# 2_4G.net
KiCad netlist of a schematic drawn in Altium Designer
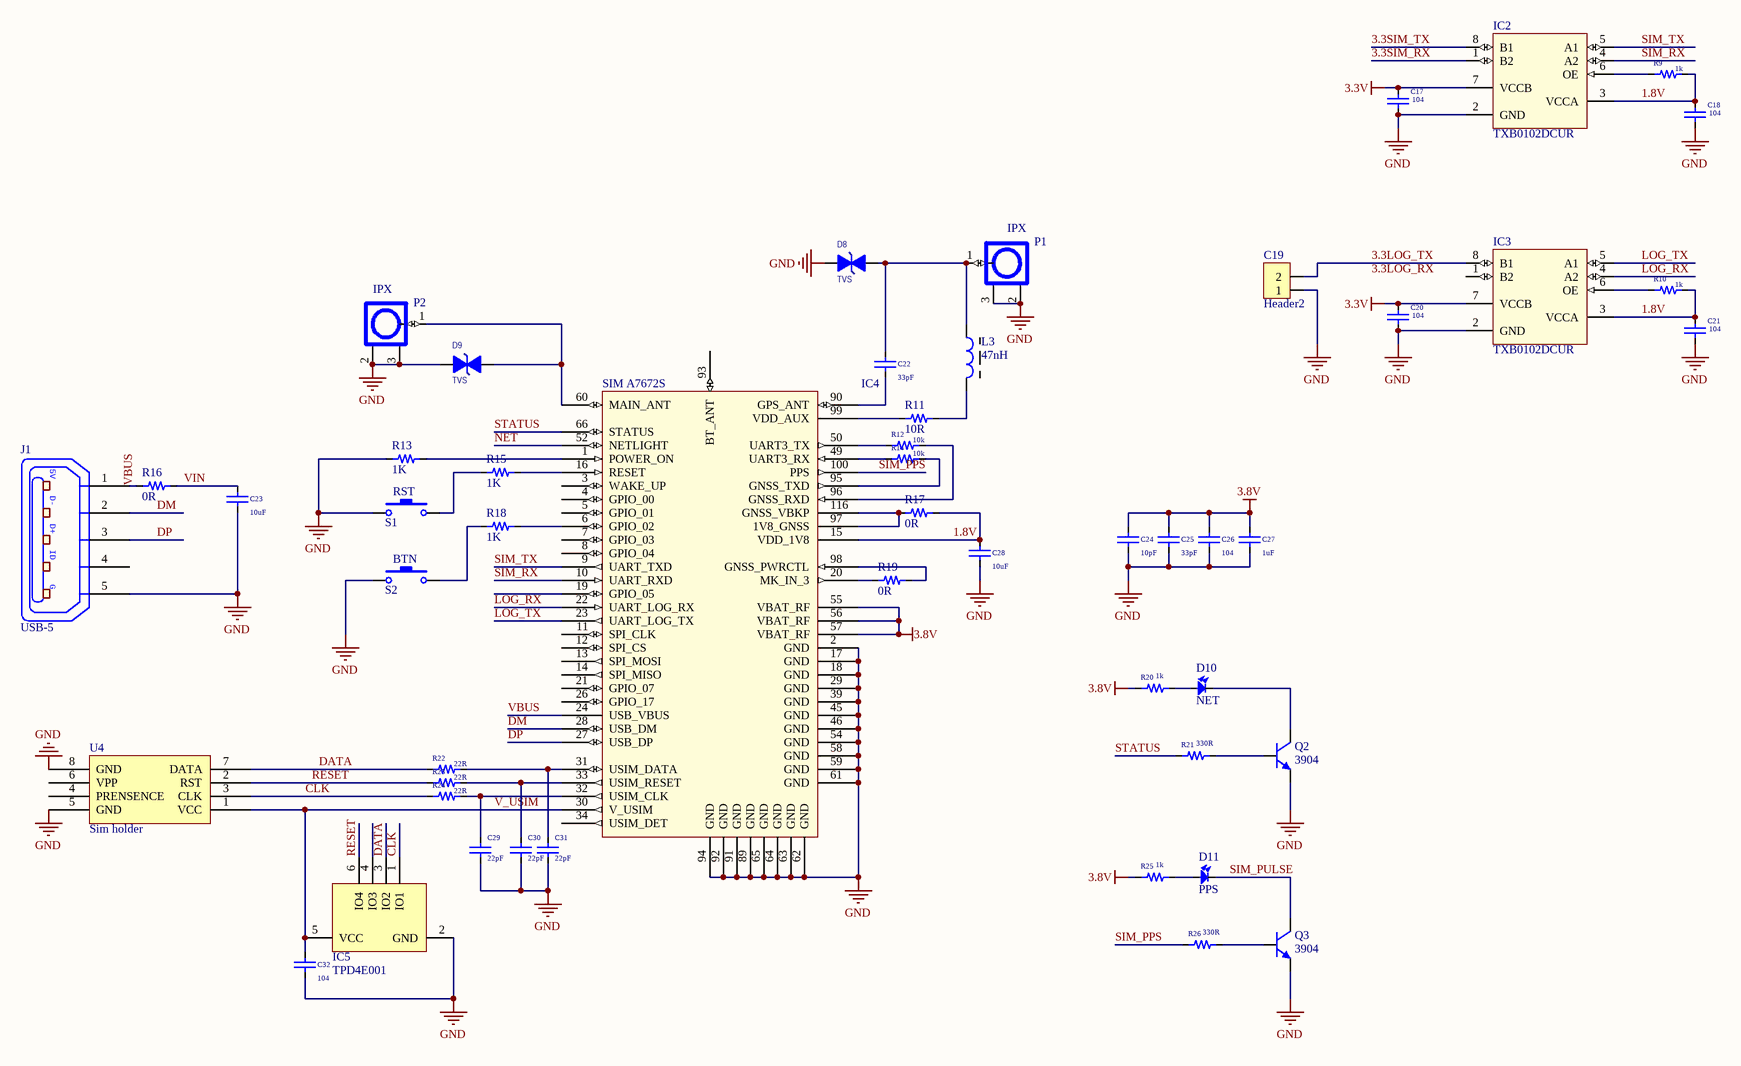
[diagram p0: 2. 4G.SchDoc]

(export (version "E")
  (design (tool "Eeschema 10.0.6"))
  (components
    (comp (ref "C17")
      (value "104")
      (footprint "CAP_0603")
      (description "Capacitor")
      (fields (field (name "PUBLISHER") "Altium Limited"))
      (libsource (lib "My Library") (part "CapSMD"))
    )
    (comp (ref "C18")
      (value "104")
      (footprint "CAP_0603")
      (description "Capacitor")
      (fields (field (name "PUBLISHER") "Altium Limited"))
      (libsource (lib "My Library") (part "CapSMD"))
    )
    (comp (ref "C19")
      (value "Header2")
      (footprint "JP2")
      (description "Header IDC, 2 x 1 Pin Vertical 2.54mm Pitch (Non-Boxed, Male)")
      (fields
        (field (name "MANUFACTURER") "Würth Elektronik eiSos GmbH")
        (field (name "PARTNO") "613002143121")
        (field (name "CREATED BY") "Karrer Zheng")
      )
      (libsource (lib "My Library") (part "Header2"))
    )
    (comp (ref "C20")
      (value "104")
      (footprint "CAP_0603")
      (description "Capacitor")
      (fields (field (name "PUBLISHER") "Altium Limited"))
      (libsource (lib "My Library") (part "CapSMD"))
    )
    (comp (ref "C21")
      (value "104")
      (footprint "CAP_0603")
      (description "Capacitor")
      (fields (field (name "PUBLISHER") "Altium Limited"))
      (libsource (lib "My Library") (part "CapSMD"))
    )
    (comp (ref "C22")
      (value "33pF")
      (footprint "CAP_0603")
      (description "Capacitor")
      (fields (field (name "PUBLISHER") "Altium Limited"))
      (libsource (lib "My Library") (part "CapSMD"))
    )
    (comp (ref "C23")
      (value "10uF")
      (footprint "CAP_0603")
      (description "Capacitor")
      (fields (field (name "PUBLISHER") "Altium Limited"))
      (libsource (lib "My Library") (part "CapSMD"))
    )
    (comp (ref "C24")
      (value "10pF")
      (footprint "CAP_0603")
      (description "Capacitor")
      (fields (field (name "PUBLISHER") "Altium Limited"))
      (libsource (lib "My Library") (part "CapSMD"))
    )
    (comp (ref "C25")
      (value "33pF")
      (footprint "CAP_0603")
      (description "Capacitor")
      (fields (field (name "PUBLISHER") "Altium Limited"))
      (libsource (lib "My Library") (part "CapSMD"))
    )
    (comp (ref "C26")
      (value "104")
      (footprint "CAP_0603")
      (description "Capacitor")
      (fields (field (name "PUBLISHER") "Altium Limited"))
      (libsource (lib "My Library") (part "CapSMD"))
    )
    (comp (ref "C27")
      (value "1uF")
      (footprint "CAP_0603")
      (description "Capacitor")
      (fields (field (name "PUBLISHER") "Altium Limited"))
      (libsource (lib "My Library") (part "CapSMD"))
    )
    (comp (ref "C28")
      (value "10uF")
      (footprint "CAP_0603")
      (description "Capacitor")
      (fields (field (name "PUBLISHER") "Altium Limited"))
      (libsource (lib "My Library") (part "CapSMD"))
    )
    (comp (ref "C29")
      (value "22pF")
      (footprint "CAP_0603")
      (description "Capacitor")
      (fields (field (name "PUBLISHER") "Altium Limited"))
      (libsource (lib "My Library") (part "CapSMD"))
    )
    (comp (ref "C30")
      (value "22pF")
      (footprint "CAP_0603")
      (description "Capacitor")
      (fields (field (name "PUBLISHER") "Altium Limited"))
      (libsource (lib "My Library") (part "CapSMD"))
    )
    (comp (ref "C31")
      (value "22pF")
      (footprint "CAP_0603")
      (description "Capacitor")
      (fields (field (name "PUBLISHER") "Altium Limited"))
      (libsource (lib "My Library") (part "CapSMD"))
    )
    (comp (ref "C32")
      (value "104")
      (footprint "CAP_0603")
      (description "Capacitor")
      (fields (field (name "PUBLISHER") "Altium Limited"))
      (libsource (lib "My Library") (part "CapSMD"))
    )
    (comp (ref "D8")
      (value "TVS")
      (footprint "RES-SMD-0402")
      (description "TVS DIODE 4VWM 1005")
      (fields
        (field (name "MANUFACTURER") "Murata Electronics")
        (field (name "PART NUMBER") "LXES15AAA1-153")
      )
      (libsource (lib "My Library") (part "TVS"))
    )
    (comp (ref "D9")
      (value "TVS")
      (footprint "RES-SMD-0402")
      (description "TVS DIODE 4VWM 1005")
      (fields
        (field (name "MANUFACTURER") "Murata Electronics")
        (field (name "PART NUMBER") "LXES15AAA1-153")
      )
      (libsource (lib "My Library") (part "TVS"))
    )
    (comp (ref "D10")
      (value "NET")
      (footprint "LED-3")
      (description "LED Single colour Green and Red")
      (libsource (lib "My Library") (part "LED"))
    )
    (comp (ref "D11")
      (value "PPS")
      (footprint "LED-0603-Red")
      (description "LED Single colour Green and Red")
      (libsource (lib "My Library") (part "LED"))
    )
    (comp (ref "IC2")
      (value "TXB0102DCUR")
      (footprint "TXB0102DCUR")
      (description "IC TRNSLTR BIDIRECTIONAL US8")
      (fields (field (name "MANUFACTURER") "Texas Instruments"))
      (libsource (lib "My Library") (part "TXB0102DCUR"))
    )
    (comp (ref "IC3")
      (value "TXB0102DCUR")
      (footprint "TXB0102DCUR")
      (description "IC TRNSLTR BIDIRECTIONAL US8")
      (fields (field (name "MANUFACTURER") "Texas Instruments"))
      (libsource (lib "My Library") (part "TXB0102DCUR"))
    )
    (comp (ref "IC4")
      (value "SIM A7672S")
      (footprint "SIM A7672S")
      (description "SIM A7672S-CAT-M1")
      (libsource (lib "My Library") (part "SIM A7672S"))
    )
    (comp (ref "IC5")
      (value "TPD4E001")
      (footprint "TPD4E001")
      (fields (field (name "MANUFACTURER") "Texas Instruments") (field (name "PART NUMBER") "TPD4E001RDBVR"))
      (libsource (lib "My Library") (part "TPD4E001_1"))
    )
    (comp (ref "J1")
      (value "USB-5")
      (footprint "MICROUSB")
      (fields (field (name "MANUFACTURER") "FCI"))
      (libsource (lib "Anh_Trung") (part "USB-5"))
    )
    (comp (ref "L3")
      (value "47nH")
      (footprint "RES-SMD-0603")
      (description "FIXED IND 47NH 300MA 700MOHM SMD")
      (fields (field (name "MANUFACTURER") "Taiyo Yuden") (field (name "PART NUMBER") "HK160847NJ-T"))
      (libsource (lib "Anh_Trung") (part "Inductor Ferit"))
    )
    (comp (ref "P1")
      (value "IPX")
      (footprint "IPXS")
      (description "Antenna GSM GPS")
      (fields
        (field (name "MANUFACTURER") "TE Connectivity AMP Connectors")
        (field (name "PART NUMBER") "2334884-1")
      )
      (libsource (lib "") (part "IPXSx66_1"))
    )
    (comp (ref "P2")
      (value "IPX")
      (footprint "IPXS")
      (description "Antenna GSM GPS")
      (fields
        (field (name "MANUFACTURER") "TE Connectivity AMP Connectors")
        (field (name "PART NUMBER") "2334884-1")
      )
      (libsource (lib "Anh_Trung") (part "IPXSx66"))
    )
    (comp (ref "Q2") (value "3904") (footprint "MMBT3904") (libsource (lib "My Library") (part "MMBT3904")))
    (comp (ref "Q3") (value "3904") (footprint "MMBT3904") (libsource (lib "My Library") (part "MMBT3904")))
    (comp (ref "R9")
      (value "1k")
      (footprint "RES-SMD-0603")
      (description "Resistor")
      (fields
        (field (name "MANUFACTURER") "Generic Components")
        (field (name "PUBLISHER") "Altium Hobart Technology Centre")
      )
      (libsource (lib "My Library") (part "Resistor - SMD"))
    )
    (comp (ref "R10")
      (value "1k")
      (footprint "RES-SMD-0603")
      (description "Resistor")
      (fields
        (field (name "MANUFACTURER") "Generic Components")
        (field (name "PUBLISHER") "Altium Hobart Technology Centre")
      )
      (libsource (lib "My Library") (part "Resistor - SMD"))
    )
    (comp (ref "R11")
      (value "10R")
      (footprint "RES-SMD-0603")
      (description "Resistor")
      (fields
        (field (name "MANUFACTURER") "Generic Components")
        (field (name "PUBLISHER") "Altium Hobart Technology Centre")
      )
      (libsource (lib "My Library") (part "Resistor - SMD"))
    )
    (comp (ref "R12")
      (value "10k")
      (footprint "RES-SMD-0603")
      (description "Resistor")
      (fields
        (field (name "MANUFACTURER") "Generic Components")
        (field (name "PUBLISHER") "Altium Hobart Technology Centre")
      )
      (libsource (lib "My Library") (part "Resistor - SMD"))
    )
    (comp (ref "R13")
      (value "1K")
      (footprint "RES-SMD-0603")
      (description "Resistor")
      (fields
        (field (name "MANUFACTURER") "Generic Components")
        (field (name "PUBLISHER") "Altium Hobart Technology Centre")
      )
      (libsource (lib "My Library") (part "Resistor - SMD"))
    )
    (comp (ref "R14")
      (value "10k")
      (footprint "RES-SMD-0603")
      (description "Resistor")
      (fields
        (field (name "MANUFACTURER") "Generic Components")
        (field (name "PUBLISHER") "Altium Hobart Technology Centre")
      )
      (libsource (lib "My Library") (part "Resistor - SMD"))
    )
    (comp (ref "R15")
      (value "1K")
      (footprint "RES-SMD-0603")
      (description "Resistor")
      (fields
        (field (name "MANUFACTURER") "Generic Components")
        (field (name "PUBLISHER") "Altium Hobart Technology Centre")
      )
      (libsource (lib "My Library") (part "Resistor - SMD"))
    )
    (comp (ref "R16")
      (value "0R")
      (footprint "RES-SMD-0603")
      (description "Resistor")
      (fields
        (field (name "MANUFACTURER") "Generic Components")
        (field (name "PUBLISHER") "Altium Hobart Technology Centre")
      )
      (libsource (lib "My Library") (part "Resistor - SMD"))
    )
    (comp (ref "R17")
      (value "0R")
      (footprint "RES-SMD-0603")
      (description "Resistor")
      (fields
        (field (name "MANUFACTURER") "Generic Components")
        (field (name "PUBLISHER") "Altium Hobart Technology Centre")
      )
      (libsource (lib "My Library") (part "Resistor - SMD"))
    )
    (comp (ref "R18")
      (value "1K")
      (footprint "RES-SMD-0603")
      (description "Resistor")
      (fields
        (field (name "MANUFACTURER") "Generic Components")
        (field (name "PUBLISHER") "Altium Hobart Technology Centre")
      )
      (libsource (lib "My Library") (part "Resistor - SMD"))
    )
    (comp (ref "R19")
      (value "0R")
      (footprint "RES-SMD-0603")
      (description "Resistor")
      (fields
        (field (name "MANUFACTURER") "Generic Components")
        (field (name "PUBLISHER") "Altium Hobart Technology Centre")
      )
      (libsource (lib "My Library") (part "Resistor - SMD"))
    )
    (comp (ref "R20")
      (value "1k")
      (footprint "RES-SMD-0603")
      (description "Resistor")
      (fields
        (field (name "MANUFACTURER") "Generic Components")
        (field (name "PUBLISHER") "Altium Hobart Technology Centre")
      )
      (libsource (lib "My Library") (part "Resistor - SMD"))
    )
    (comp (ref "R21")
      (value "330R")
      (footprint "RES-SMD-0603")
      (description "Resistor")
      (fields
        (field (name "MANUFACTURER") "Generic Components")
        (field (name "PUBLISHER") "Altium Hobart Technology Centre")
      )
      (libsource (lib "My Library") (part "Resistor - SMD"))
    )
    (comp (ref "R22")
      (value "22R")
      (footprint "RES-SMD-0603")
      (description "Resistor")
      (fields
        (field (name "MANUFACTURER") "Generic Components")
        (field (name "PUBLISHER") "Altium Hobart Technology Centre")
      )
      (libsource (lib "My Library") (part "Resistor - SMD"))
    )
    (comp (ref "R23")
      (value "22R")
      (footprint "RES-SMD-0603")
      (description "Resistor")
      (fields
        (field (name "MANUFACTURER") "Generic Components")
        (field (name "PUBLISHER") "Altium Hobart Technology Centre")
      )
      (libsource (lib "My Library") (part "Resistor - SMD"))
    )
    (comp (ref "R24")
      (value "22R")
      (footprint "RES-SMD-0603")
      (description "Resistor")
      (fields
        (field (name "MANUFACTURER") "Generic Components")
        (field (name "PUBLISHER") "Altium Hobart Technology Centre")
      )
      (libsource (lib "My Library") (part "Resistor - SMD"))
    )
    (comp (ref "R25")
      (value "1k")
      (footprint "RES-SMD-0603")
      (description "Resistor")
      (fields
        (field (name "MANUFACTURER") "Generic Components")
        (field (name "PUBLISHER") "Altium Hobart Technology Centre")
      )
      (libsource (lib "My Library") (part "Resistor - SMD"))
    )
    (comp (ref "R26")
      (value "330R")
      (footprint "RES-SMD-0603")
      (description "Resistor")
      (fields
        (field (name "MANUFACTURER") "Generic Components")
        (field (name "PUBLISHER") "Altium Hobart Technology Centre")
      )
      (libsource (lib "My Library") (part "Resistor - SMD"))
    )
    (comp (ref "S1")
      (value "RST")
      (footprint "SW-SMD")
      (description "Switch")
      (fields (field (name "PUBLISHER") "Altium Limited"))
      (libsource (lib "My Library") (part "SW-SMD"))
    )
    (comp (ref "S2")
      (value "BTN")
      (footprint "SW-SMD")
      (description "Switch")
      (fields (field (name "PUBLISHER") "Altium Limited"))
      (libsource (lib "My Library") (part "SW-SMD"))
    )
    (comp (ref "U4")
      (value "Sim holder")
      (footprint "SIM_MicroSIM 6P Flip")
      (libsource (lib "Anh_Trung") (part "Component_1"))
    )
  )
  (nets
    (net (code "1") (name "/1.8V") (class "Default")
      (node (ref "C18") (pin "2") (pinfunction "2_2") (pintype "passive"))
      (node (ref "C21") (pin "2") (pinfunction "2_2") (pintype "passive"))
      (node (ref "C28") (pin "2") (pinfunction "2_2") (pintype "passive"))
      (node (ref "IC2") (pin "3") (pinfunction "VCCA_3") (pintype "power_in"))
      (node (ref "IC3") (pin "3") (pinfunction "VCCA_3") (pintype "power_in"))
      (node (ref "IC4") (pin "15") (pinfunction "VDD_1V8_15") (pintype "passive"))
      (node (ref "R10") (pin "1") (pinfunction "1_1") (pintype "passive"))
      (node (ref "R17") (pin "2") (pinfunction "2_2") (pintype "passive"))
      (node (ref "R9") (pin "1") (pinfunction "1_1") (pintype "passive"))
    )
    (net (code "3") (name "/3.3LOG_TX") (class "Default")
      (node (ref "C19") (pin "2") (pinfunction "2_2") (pintype "passive"))
      (node (ref "IC3") (pin "8") (pinfunction "B1_8") (pintype "bidirectional"))
    )
    (net (code "4") (name "/3.3SIM_RX") (class "Default")
      (node (ref "IC2") (pin "1") (pinfunction "B2_1") (pintype "bidirectional"))
    )
    (net (code "5") (name "/3.3SIM_TX") (class "Default")
      (node (ref "IC2") (pin "8") (pinfunction "B1_8") (pintype "bidirectional"))
    )
    (net (code "6") (name "/CLK") (class "Default")
      (node (ref "IC5") (pin "1") (pinfunction "IO1_1") (pintype "passive"))
      (node (ref "R24") (pin "2") (pinfunction "2_2") (pintype "passive"))
      (node (ref "U4") (pin "3") (pinfunction "CLK_3") (pintype "passive"))
    )
    (net (code "7") (name "/DATA") (class "Default")
      (node (ref "IC5") (pin "3") (pinfunction "IO2_3") (pintype "passive"))
      (node (ref "R22") (pin "2") (pinfunction "2_2") (pintype "passive"))
      (node (ref "U4") (pin "7") (pinfunction "DATA_7") (pintype "passive"))
    )
    (net (code "8") (name "/DM") (class "Default")
      (node (ref "IC4") (pin "28") (pinfunction "USB_DM_28") (pintype "bidirectional"))
      (node (ref "J1") (pin "2") (pinfunction "P2_2") (pintype "passive"))
    )
    (net (code "9") (name "/DP") (class "Default")
      (node (ref "IC4") (pin "27") (pinfunction "USB_DP_27") (pintype "bidirectional"))
      (node (ref "J1") (pin "3") (pinfunction "P3_3") (pintype "passive"))
    )
    (net (code "10") (name "/LOG_RX") (class "Default")
      (node (ref "IC3") (pin "4") (pinfunction "A2_4") (pintype "bidirectional"))
      (node (ref "IC4") (pin "22") (pinfunction "UART_LOG_RX_22") (pintype "input"))
    )
    (net (code "11") (name "/LOG_TX") (class "Default")
      (node (ref "IC3") (pin "5") (pinfunction "A1_5") (pintype "bidirectional"))
      (node (ref "IC4") (pin "23") (pinfunction "UART_LOG_TX_23") (pintype "output"))
    )
    (net (code "12") (name "/NET") (class "Default")
      (node (ref "IC4") (pin "52") (pinfunction "NETLIGHT_52") (pintype "bidirectional"))
    )
    (net (code "13") (name "/RESET") (class "Default")
      (node (ref "IC5") (pin "6") (pinfunction "IO4_6") (pintype "passive"))
      (node (ref "R23") (pin "2") (pinfunction "2_2") (pintype "passive"))
      (node (ref "U4") (pin "2") (pinfunction "RST_2") (pintype "passive"))
    )
    (net (code "14") (name "/SIM_PPS") (class "Default")
      (node (ref "IC4") (pin "100") (pinfunction "PPS_100") (pintype "output"))
      (node (ref "R26") (pin "2") (pinfunction "2_2") (pintype "passive"))
    )
    (net (code "15") (name "/SIM_PULSE") (class "Default")
      (node (ref "D11") (pin "2") (pinfunction "2_2") (pintype "passive"))
      (node (ref "Q3") (pin "3") (pinfunction "C_3") (pintype "passive"))
    )
    (net (code "16") (name "/SIM_RX") (class "Default")
      (node (ref "IC2") (pin "4") (pinfunction "A2_4") (pintype "bidirectional"))
      (node (ref "IC4") (pin "10") (pinfunction "UART_RXD_10") (pintype "input"))
    )
    (net (code "17") (name "/SIM_TX") (class "Default")
      (node (ref "IC2") (pin "5") (pinfunction "A1_5") (pintype "bidirectional"))
      (node (ref "IC4") (pin "9") (pinfunction "UART_TXD_9") (pintype "output"))
    )
    (net (code "18") (name "/STATUS") (class "Default")
      (node (ref "IC4") (pin "66") (pinfunction "STATUS_66") (pintype "bidirectional"))
      (node (ref "R21") (pin "2") (pinfunction "2_2") (pintype "passive"))
    )
    (net (code "19") (name "/VBUS") (class "Default")
      (node (ref "IC4") (pin "24") (pinfunction "USB_VBUS_24") (pintype "passive"))
      (node (ref "J1") (pin "1") (pinfunction "P1_1") (pintype "passive"))
      (node (ref "R16") (pin "1") (pinfunction "1_1") (pintype "passive"))
    )
    (net (code "20") (name "/VIN") (class "Default")
      (node (ref "C23") (pin "2") (pinfunction "2_2") (pintype "passive"))
      (node (ref "R16") (pin "2") (pinfunction "2_2") (pintype "passive"))
    )
    (net (code "21") (name "/V_USIM") (class "Default")
      (node (ref "C32") (pin "2") (pinfunction "2_2") (pintype "passive"))
      (node (ref "IC4") (pin "30") (pinfunction "V_USIM_30") (pintype "output"))
      (node (ref "IC5") (pin "5") (pinfunction "VCC_5") (pintype "passive"))
      (node (ref "U4") (pin "1") (pinfunction "VCC_1") (pintype "passive"))
    )
    (net (code "22") (name "3.3V") (class "Default")
      (node (ref "C17") (pin "2") (pinfunction "2_2") (pintype "passive"))
      (node (ref "C20") (pin "2") (pinfunction "2_2") (pintype "passive"))
      (node (ref "IC2") (pin "7") (pinfunction "VCCB_7") (pintype "power_in"))
      (node (ref "IC3") (pin "7") (pinfunction "VCCB_7") (pintype "power_in"))
    )
    (net (code "23") (name "3.8V") (class "Default")
      (node (ref "C24") (pin "2") (pinfunction "2_2") (pintype "passive"))
      (node (ref "C25") (pin "2") (pinfunction "2_2") (pintype "passive"))
      (node (ref "C26") (pin "2") (pinfunction "2_2") (pintype "passive"))
      (node (ref "C27") (pin "2") (pinfunction "2_2") (pintype "passive"))
      (node (ref "IC4") (pin "55") (pinfunction "VBAT_RF_55") (pintype "passive"))
      (node (ref "IC4") (pin "56") (pinfunction "VBAT_RF_56") (pintype "passive"))
      (node (ref "IC4") (pin "57") (pinfunction "VBAT_RF_57") (pintype "passive"))
      (node (ref "R20") (pin "2") (pinfunction "2_2") (pintype "passive"))
      (node (ref "R25") (pin "2") (pinfunction "2_2") (pintype "passive"))
    )
    (net (code "24") (name "GND") (class "Default")
      (node (ref "C17") (pin "1") (pinfunction "1_1") (pintype "passive"))
      (node (ref "C18") (pin "1") (pinfunction "1_1") (pintype "passive"))
      (node (ref "C19") (pin "1") (pinfunction "1_1") (pintype "passive"))
      (node (ref "C20") (pin "1") (pinfunction "1_1") (pintype "passive"))
      (node (ref "C21") (pin "1") (pinfunction "1_1") (pintype "passive"))
      (node (ref "C23") (pin "1") (pinfunction "1_1") (pintype "passive"))
      (node (ref "C24") (pin "1") (pinfunction "1_1") (pintype "passive"))
      (node (ref "C25") (pin "1") (pinfunction "1_1") (pintype "passive"))
      (node (ref "C26") (pin "1") (pinfunction "1_1") (pintype "passive"))
      (node (ref "C27") (pin "1") (pinfunction "1_1") (pintype "passive"))
      (node (ref "C28") (pin "1") (pinfunction "1_1") (pintype "passive"))
      (node (ref "C29") (pin "1") (pinfunction "1_1") (pintype "passive"))
      (node (ref "C30") (pin "1") (pinfunction "1_1") (pintype "passive"))
      (node (ref "C31") (pin "1") (pinfunction "1_1") (pintype "passive"))
      (node (ref "C32") (pin "1") (pinfunction "1_1") (pintype "passive"))
      (node (ref "D8") (pin "2") (pinfunction "K_2") (pintype "passive"))
      (node (ref "D9") (pin "2") (pinfunction "K_2") (pintype "passive"))
      (node (ref "IC2") (pin "2") (pinfunction "GND_2") (pintype "power_in"))
      (node (ref "IC3") (pin "2") (pinfunction "GND_2") (pintype "power_in"))
      (node (ref "IC4") (pin "17") (pinfunction "GND_17") (pintype "passive"))
      (node (ref "IC4") (pin "18") (pinfunction "GND_18") (pintype "passive"))
      (node (ref "IC4") (pin "2") (pinfunction "GND_2") (pintype "passive"))
      (node (ref "IC4") (pin "29") (pinfunction "GND_29") (pintype "passive"))
      (node (ref "IC4") (pin "39") (pinfunction "GND_39") (pintype "passive"))
      (node (ref "IC4") (pin "45") (pinfunction "GND_45") (pintype "passive"))
      (node (ref "IC4") (pin "46") (pinfunction "GND_46") (pintype "passive"))
      (node (ref "IC4") (pin "54") (pinfunction "GND_54") (pintype "passive"))
      (node (ref "IC4") (pin "58") (pinfunction "GND_58") (pintype "passive"))
      (node (ref "IC4") (pin "59") (pinfunction "GND_59") (pintype "passive"))
      (node (ref "IC4") (pin "61") (pinfunction "GND_61") (pintype "passive"))
      (node (ref "IC4") (pin "62") (pinfunction "GND_62") (pintype "passive"))
      (node (ref "IC4") (pin "63") (pinfunction "GND_63") (pintype "passive"))
      (node (ref "IC4") (pin "64") (pinfunction "GND_64") (pintype "passive"))
      (node (ref "IC4") (pin "65") (pinfunction "GND_65") (pintype "passive"))
      (node (ref "IC4") (pin "89") (pinfunction "GND_89") (pintype "passive"))
      (node (ref "IC4") (pin "91") (pinfunction "GND_91") (pintype "passive"))
      (node (ref "IC4") (pin "92") (pinfunction "GND_92") (pintype "passive"))
      (node (ref "IC4") (pin "94") (pinfunction "GND_94") (pintype "passive"))
      (node (ref "IC5") (pin "2") (pinfunction "GND_2") (pintype "passive"))
      (node (ref "J1") (pin "5") (pinfunction "P5_5") (pintype "passive"))
      (node (ref "P1") (pin "2") (pintype "passive"))
      (node (ref "P1") (pin "3") (pintype "passive"))
      (node (ref "P2") (pin "2") (pintype "passive"))
      (node (ref "P2") (pin "3") (pintype "passive"))
      (node (ref "Q2") (pin "2") (pinfunction "E_2") (pintype "passive"))
      (node (ref "Q3") (pin "2") (pinfunction "E_2") (pintype "passive"))
      (node (ref "R13") (pin "1") (pinfunction "1_1") (pintype "passive"))
      (node (ref "S1") (pin "1") (pinfunction "1_1") (pintype "passive"))
      (node (ref "S2") (pin "1") (pinfunction "1_1") (pintype "passive"))
      (node (ref "U4") (pin "5") (pinfunction "GND_5") (pintype "passive"))
      (node (ref "U4") (pin "8") (pinfunction "GND_8") (pintype "passive"))
    )
    (net (code "25") (name "Net-(D8-A)") (class "Default")
      (node (ref "C22") (pin "2") (pinfunction "2_2") (pintype "passive"))
      (node (ref "D8") (pin "1") (pinfunction "A_1") (pintype "passive"))
      (node (ref "L3") (pin "1") (pinfunction "1_1") (pintype "passive"))
      (node (ref "P1") (pin "1") (pintype "bidirectional"))
    )
    (net (code "26") (name "Net-(D9-A)") (class "Default")
      (node (ref "D9") (pin "1") (pinfunction "A_1") (pintype "passive"))
      (node (ref "IC4") (pin "60") (pinfunction "MAIN_ANT_60") (pintype "bidirectional"))
      (node (ref "P2") (pin "1") (pintype "bidirectional"))
    )
    (net (code "27") (name "Net-(D10-Pad1)") (class "Default")
      (node (ref "D10") (pin "1") (pinfunction "1_1") (pintype "passive"))
      (node (ref "R20") (pin "1") (pinfunction "1_1") (pintype "passive"))
    )
    (net (code "28") (name "Net-(D11-Pad1)") (class "Default")
      (node (ref "D11") (pin "1") (pinfunction "1_1") (pintype "passive"))
      (node (ref "R25") (pin "1") (pinfunction "1_1") (pintype "passive"))
    )
    (net (code "29") (name "Net-(IC2-OE)") (class "Default")
      (node (ref "IC2") (pin "6") (pinfunction "OE_6") (pintype "input"))
      (node (ref "R9") (pin "2") (pinfunction "2_2") (pintype "passive"))
    )
    (net (code "30") (name "Net-(IC3-OE)") (class "Default")
      (node (ref "IC3") (pin "6") (pinfunction "OE_6") (pintype "input"))
      (node (ref "R10") (pin "2") (pinfunction "2_2") (pintype "passive"))
    )
    (net (code "31") (name "Net-(IC4-1V8_GNSS)") (class "Default")
      (node (ref "IC4") (pin "116") (pinfunction "GNSS_VBKP_116") (pintype "passive"))
      (node (ref "IC4") (pin "97") (pinfunction "1V8_GNSS_97") (pintype "passive"))
      (node (ref "R17") (pin "1") (pinfunction "1_1") (pintype "passive"))
    )
    (net (code "32") (name "Net-(IC4-GNSS_PWRCTL)") (class "Default")
      (node (ref "IC4") (pin "98") (pinfunction "GNSS_PWRCTL_98") (pintype "input"))
      (node (ref "R19") (pin "2") (pinfunction "2_2") (pintype "passive"))
    )
    (net (code "33") (name "Net-(IC4-GNSS_RXD)") (class "Default")
      (node (ref "IC4") (pin "96") (pinfunction "GNSS_RXD_96") (pintype "input"))
      (node (ref "R12") (pin "1") (pinfunction "1_1") (pintype "passive"))
    )
    (net (code "34") (name "Net-(IC4-GNSS_TXD)") (class "Default")
      (node (ref "IC4") (pin "95") (pinfunction "GNSS_TXD_95") (pintype "output"))
      (node (ref "R14") (pin "1") (pinfunction "1_1") (pintype "passive"))
    )
    (net (code "35") (name "Net-(IC4-GPIO_02)") (class "Default")
      (node (ref "IC4") (pin "6") (pinfunction "GPIO_02_6") (pintype "bidirectional"))
      (node (ref "R18") (pin "1") (pinfunction "1_1") (pintype "passive"))
    )
    (net (code "36") (name "Net-(IC4-GPS_ANT)") (class "Default")
      (node (ref "C22") (pin "1") (pinfunction "1_1") (pintype "passive"))
      (node (ref "IC4") (pin "90") (pinfunction "GPS_ANT_90") (pintype "bidirectional"))
    )
    (net (code "37") (name "Net-(IC4-MK_IN_3)") (class "Default")
      (node (ref "IC4") (pin "20") (pinfunction "MK_IN_3_20") (pintype "output"))
      (node (ref "R19") (pin "1") (pinfunction "1_1") (pintype "passive"))
    )
    (net (code "38") (name "Net-(IC4-POWER_ON)") (class "Default")
      (node (ref "IC4") (pin "1") (pinfunction "POWER_ON_1") (pintype "input"))
      (node (ref "R13") (pin "2") (pinfunction "2_2") (pintype "passive"))
    )
    (net (code "39") (name "Net-(IC4-RESET)") (class "Default")
      (node (ref "IC4") (pin "16") (pinfunction "RESET_16") (pintype "input"))
      (node (ref "R15") (pin "2") (pinfunction "2_2") (pintype "passive"))
    )
    (net (code "40") (name "Net-(IC4-UART3_RX)") (class "Default")
      (node (ref "IC4") (pin "49") (pinfunction "UART3_RX_49") (pintype "input"))
      (node (ref "R14") (pin "2") (pinfunction "2_2") (pintype "passive"))
    )
    (net (code "41") (name "Net-(IC4-UART3_TX)") (class "Default")
      (node (ref "IC4") (pin "50") (pinfunction "UART3_TX_50") (pintype "output"))
      (node (ref "R12") (pin "2") (pinfunction "2_2") (pintype "passive"))
    )
    (net (code "42") (name "Net-(IC4-USIM_CLK)") (class "Default")
      (node (ref "C29") (pin "2") (pinfunction "2_2") (pintype "passive"))
      (node (ref "IC4") (pin "32") (pinfunction "USIM_CLK_32") (pintype "output"))
      (node (ref "R24") (pin "1") (pinfunction "1_1") (pintype "passive"))
    )
    (net (code "43") (name "Net-(IC4-USIM_DATA)") (class "Default")
      (node (ref "C31") (pin "2") (pinfunction "2_2") (pintype "passive"))
      (node (ref "IC4") (pin "31") (pinfunction "USIM_DATA_31") (pintype "bidirectional"))
      (node (ref "R22") (pin "1") (pinfunction "1_1") (pintype "passive"))
    )
    (net (code "44") (name "Net-(IC4-USIM_RESET)") (class "Default")
      (node (ref "C30") (pin "2") (pinfunction "2_2") (pintype "passive"))
      (node (ref "IC4") (pin "33") (pinfunction "USIM_RESET_33") (pintype "output"))
      (node (ref "R23") (pin "1") (pinfunction "1_1") (pintype "passive"))
    )
    (net (code "45") (name "Net-(IC4-VDD_AUX)") (class "Default")
      (node (ref "IC4") (pin "99") (pinfunction "VDD_AUX_99") (pintype "passive"))
      (node (ref "R11") (pin "1") (pinfunction "1_1") (pintype "passive"))
    )
    (net (code "46") (name "Net-(L3-Pad2)") (class "Default")
      (node (ref "L3") (pin "2") (pinfunction "2_2") (pintype "passive"))
      (node (ref "R11") (pin "2") (pinfunction "2_2") (pintype "passive"))
    )
    (net (code "47") (name "Net-(Q2-B)") (class "Default")
      (node (ref "Q2") (pin "1") (pinfunction "B_1") (pintype "passive"))
      (node (ref "R21") (pin "1") (pinfunction "1_1") (pintype "passive"))
    )
    (net (code "48") (name "Net-(Q2-C)") (class "Default")
      (node (ref "D10") (pin "2") (pinfunction "2_2") (pintype "passive"))
      (node (ref "Q2") (pin "3") (pinfunction "C_3") (pintype "passive"))
    )
    (net (code "49") (name "Net-(Q3-B)") (class "Default")
      (node (ref "Q3") (pin "1") (pinfunction "B_1") (pintype "passive"))
      (node (ref "R26") (pin "1") (pinfunction "1_1") (pintype "passive"))
    )
    (net (code "50") (name "Net-(R15-Pad1)") (class "Default")
      (node (ref "R15") (pin "1") (pinfunction "1_1") (pintype "passive"))
      (node (ref "S1") (pin "2") (pinfunction "2_2") (pintype "passive"))
    )
    (net (code "51") (name "Net-(R18-Pad2)") (class "Default")
      (node (ref "R18") (pin "2") (pinfunction "2_2") (pintype "passive"))
      (node (ref "S2") (pin "2") (pinfunction "2_2") (pintype "passive"))
    )
    (net (code "52") (name "unconnected-(IC3-B2-Pad1)") (class "Default")
      (node (ref "IC3") (pin "1") (pinfunction "B2_1") (pintype "bidirectional"))
    )
    (net (code "53") (name "unconnected-(IC4-ADC1-Pad47)") (class "Default")
      (node (ref "IC4") (pin "47") (pinfunction "ADC1_47") (pintype "passive"))
    )
    (net (code "54") (name "unconnected-(IC4-ADC2-Pad46)") (class "Default")
      (node (ref "IC4") (pin "46") (pinfunction "ADC2_46") (pintype "passive"))
    )
    (net (code "55") (name "unconnected-(IC4-BT_ANT-Pad93)") (class "Default")
      (node (ref "IC4") (pin "93") (pinfunction "BT_ANT_93") (pintype "bidirectional"))
    )
    (net (code "56") (name "unconnected-(IC4-EAR1N-Pad25)") (class "Default")
      (node (ref "IC4") (pin "25") (pinfunction "EAR1N_25") (pintype "passive"))
    )
    (net (code "57") (name "unconnected-(IC4-EAR1P-Pad26)") (class "Default")
      (node (ref "IC4") (pin "26") (pinfunction "EAR1P_26") (pintype "passive"))
    )
    (net (code "58") (name "unconnected-(IC4-GPIO1-Pad51)") (class "Default")
      (node (ref "IC4") (pin "51") (pinfunction "GPIO1_51") (pintype "passive"))
    )
    (net (code "59") (name "unconnected-(IC4-GPIO4-Pad54)") (class "Default")
      (node (ref "IC4") (pin "54") (pinfunction "GPIO4_54") (pintype "passive"))
    )
    (net (code "60") (name "unconnected-(IC4-GPIO40-Pad49)") (class "Default")
      (node (ref "IC4") (pin "49") (pinfunction "GPIO40_49") (pintype "passive"))
    )
    (net (code "61") (name "unconnected-(IC4-GPIO41-Pad52)") (class "Default")
      (node (ref "IC4") (pin "52") (pinfunction "GPIO41_52") (pintype "passive"))
    )
    (net (code "62") (name "unconnected-(IC4-GPIO42-Pad53)") (class "Default")
      (node (ref "IC4") (pin "53") (pinfunction "GPIO42_53") (pintype "passive"))
    )
    (net (code "63") (name "unconnected-(IC4-GPIO43-Pad50)") (class "Default")
      (node (ref "IC4") (pin "50") (pinfunction "GPIO43_50") (pintype "passive"))
    )
    (net (code "64") (name "unconnected-(IC4-GPIO44-Pad48)") (class "Default")
      (node (ref "IC4") (pin "48") (pinfunction "GPIO44_48") (pintype "passive"))
    )
    (net (code "65") (name "unconnected-(IC4-GPIO_00-Pad4)") (class "Default")
      (node (ref "IC4") (pin "4") (pinfunction "GPIO_00_4") (pintype "bidirectional"))
    )
    (net (code "66") (name "unconnected-(IC4-GPIO_01-Pad5)") (class "Default")
      (node (ref "IC4") (pin "5") (pinfunction "GPIO_01_5") (pintype "bidirectional"))
    )
    (net (code "67") (name "unconnected-(IC4-GPIO_03-Pad7)") (class "Default")
      (node (ref "IC4") (pin "7") (pinfunction "GPIO_03_7") (pintype "bidirectional"))
    )
    (net (code "68") (name "unconnected-(IC4-GPIO_04-Pad8)") (class "Default")
      (node (ref "IC4") (pin "8") (pinfunction "GPIO_04_8") (pintype "bidirectional"))
    )
    (net (code "69") (name "unconnected-(IC4-GPIO_05-Pad19)") (class "Default")
      (node (ref "IC4") (pin "19") (pinfunction "GPIO_05_19") (pintype "bidirectional"))
    )
    (net (code "70") (name "unconnected-(IC4-GPIO_07-Pad21)") (class "Default")
      (node (ref "IC4") (pin "21") (pinfunction "GPIO_07_21") (pintype "bidirectional"))
    )
    (net (code "71") (name "unconnected-(IC4-GPIO_17-Pad26)") (class "Default")
      (node (ref "IC4") (pin "26") (pinfunction "GPIO_17_26") (pintype "bidirectional"))
    )
    (net (code "72") (name "unconnected-(IC4-KEYPAD_0-Pad29)") (class "Default")
      (node (ref "IC4") (pin "29") (pinfunction "KEYPAD_0_29") (pintype "passive"))
    )
    (net (code "73") (name "unconnected-(IC4-KEYPAD_1-Pad33)") (class "Default")
      (node (ref "IC4") (pin "33") (pinfunction "KEYPAD_1_33") (pintype "passive"))
    )
    (net (code "74") (name "unconnected-(IC4-KEYPAD_2-Pad30)") (class "Default")
      (node (ref "IC4") (pin "30") (pinfunction "KEYPAD_2_30") (pintype "passive"))
    )
    (net (code "75") (name "unconnected-(IC4-KEYPAD_3-Pad35)") (class "Default")
      (node (ref "IC4") (pin "35") (pinfunction "KEYPAD_3_35") (pintype "passive"))
    )
    (net (code "76") (name "unconnected-(IC4-KEYPAD_4-Pad34)") (class "Default")
      (node (ref "IC4") (pin "34") (pinfunction "KEYPAD_4_34") (pintype "passive"))
    )
    (net (code "77") (name "unconnected-(IC4-KEYSENSE_N0-Pad28)") (class "Default")
      (node (ref "IC4") (pin "28") (pinfunction "KEYSENSE_N0_28") (pintype "passive"))
    )
    (net (code "78") (name "unconnected-(IC4-KEYSENSE_N1-Pad27)") (class "Default")
      (node (ref "IC4") (pin "27") (pinfunction "KEYSENSE_N1_27") (pintype "passive"))
    )
    (net (code "79") (name "unconnected-(IC4-KEYSENSE_N2-Pad31)") (class "Default")
      (node (ref "IC4") (pin "31") (pinfunction "KEYSENSE_N2_31") (pintype "passive"))
    )
    (net (code "80") (name "unconnected-(IC4-KEYSENSE_N3-Pad32)") (class "Default")
      (node (ref "IC4") (pin "32") (pinfunction "KEYSENSE_N3_32") (pintype "passive"))
    )
    (net (code "81") (name "unconnected-(IC4-KEYSENSE_N4-Pad36)") (class "Default")
      (node (ref "IC4") (pin "36") (pinfunction "KEYSENSE_N4_36") (pintype "passive"))
    )
    (net (code "82") (name "unconnected-(IC4-MIC1N-Pad24)") (class "Default")
      (node (ref "IC4") (pin "24") (pinfunction "MIC1N_24") (pintype "passive"))
    )
    (net (code "83") (name "unconnected-(IC4-MIC1P-Pad23)") (class "Default")
      (node (ref "IC4") (pin "23") (pinfunction "MIC1P_23") (pintype "passive"))
    )
    (net (code "84") (name "unconnected-(IC4-PCM_CLK-Pad76)") (class "Default")
      (node (ref "IC4") (pin "76") (pinfunction "PCM_CLK_76") (pintype "passive"))
    )
    (net (code "85") (name "unconnected-(IC4-PCM_DIN-Pad74)") (class "Default")
      (node (ref "IC4") (pin "74") (pinfunction "PCM_DIN_74") (pintype "passive"))
    )
    (net (code "86") (name "unconnected-(IC4-PCM_DOUT-Pad73)") (class "Default")
      (node (ref "IC4") (pin "73") (pinfunction "PCM_DOUT_73") (pintype "passive"))
    )
    (net (code "87") (name "unconnected-(IC4-PCM_SYNC-Pad75)") (class "Default")
      (node (ref "IC4") (pin "75") (pinfunction "PCM_SYNC_75") (pintype "passive"))
    )
    (net (code "88") (name "unconnected-(IC4-RESERVED-Pad15)") (class "Default")
      (node (ref "IC4") (pin "15") (pinfunction "RESERVED_15") (pintype "passive"))
    )
    (net (code "89") (name "unconnected-(IC4-RESERVED-Pad16)") (class "Default")
      (node (ref "IC4") (pin "16") (pinfunction "RESERVED_16") (pintype "passive"))
    )
    (net (code "90") (name "unconnected-(IC4-SPI_CLK-Pad11)") (class "Default")
      (node (ref "IC4") (pin "11") (pinfunction "SPI_CLK_11") (pintype "bidirectional"))
    )
    (net (code "91") (name "unconnected-(IC4-SPI_CS-Pad12)") (class "Default")
      (node (ref "IC4") (pin "12") (pinfunction "SPI_CS_12") (pintype "bidirectional"))
    )
    (net (code "92") (name "unconnected-(IC4-SPI_MISO-Pad14)") (class "Default")
      (node (ref "IC4") (pin "14") (pinfunction "SPI_MISO_14") (pintype "output"))
    )
    (net (code "93") (name "unconnected-(IC4-SPI_MOSI-Pad13)") (class "Default")
      (node (ref "IC4") (pin "13") (pinfunction "SPI_MOSI_13") (pintype "output"))
    )
    (net (code "94") (name "unconnected-(IC4-SPK_M-Pad21)") (class "Default")
      (node (ref "IC4") (pin "21") (pinfunction "SPK_M_21") (pintype "passive"))
    )
    (net (code "95") (name "unconnected-(IC4-SPK_P-Pad22)") (class "Default")
      (node (ref "IC4") (pin "22") (pinfunction "SPK_P_22") (pintype "passive"))
    )
    (net (code "96") (name "unconnected-(IC4-USIM_DET-Pad34)") (class "Default")
      (node (ref "IC4") (pin "34") (pinfunction "USIM_DET_34") (pintype "output"))
    )
    (net (code "97") (name "unconnected-(IC4-WAKE_UP-Pad3)") (class "Default")
      (node (ref "IC4") (pin "3") (pinfunction "WAKE_UP_3") (pintype "bidirectional"))
    )
    (net (code "98") (name "unconnected-(IC5-IO3-Pad4)") (class "Default")
      (node (ref "IC5") (pin "4") (pinfunction "IO3_4") (pintype "passive"))
    )
    (net (code "99") (name "unconnected-(J1-P4-Pad4)") (class "Default")
      (node (ref "J1") (pin "4") (pinfunction "P4_4") (pintype "passive"))
    )
    (net (code "100") (name "unconnected-(U4-PRENSENCE-Pad4)") (class "Default")
      (node (ref "U4") (pin "4") (pinfunction "PRENSENCE_4") (pintype "passive"))
    )
    (net (code "101") (name "unconnected-(U4-VPP-Pad6)") (class "Default")
      (node (ref "U4") (pin "6") (pinfunction "VPP_6") (pintype "passive"))
    )
  )
)
